# Un_RF_old.net
KiCad netlist of a schematic drawn in EAGLE
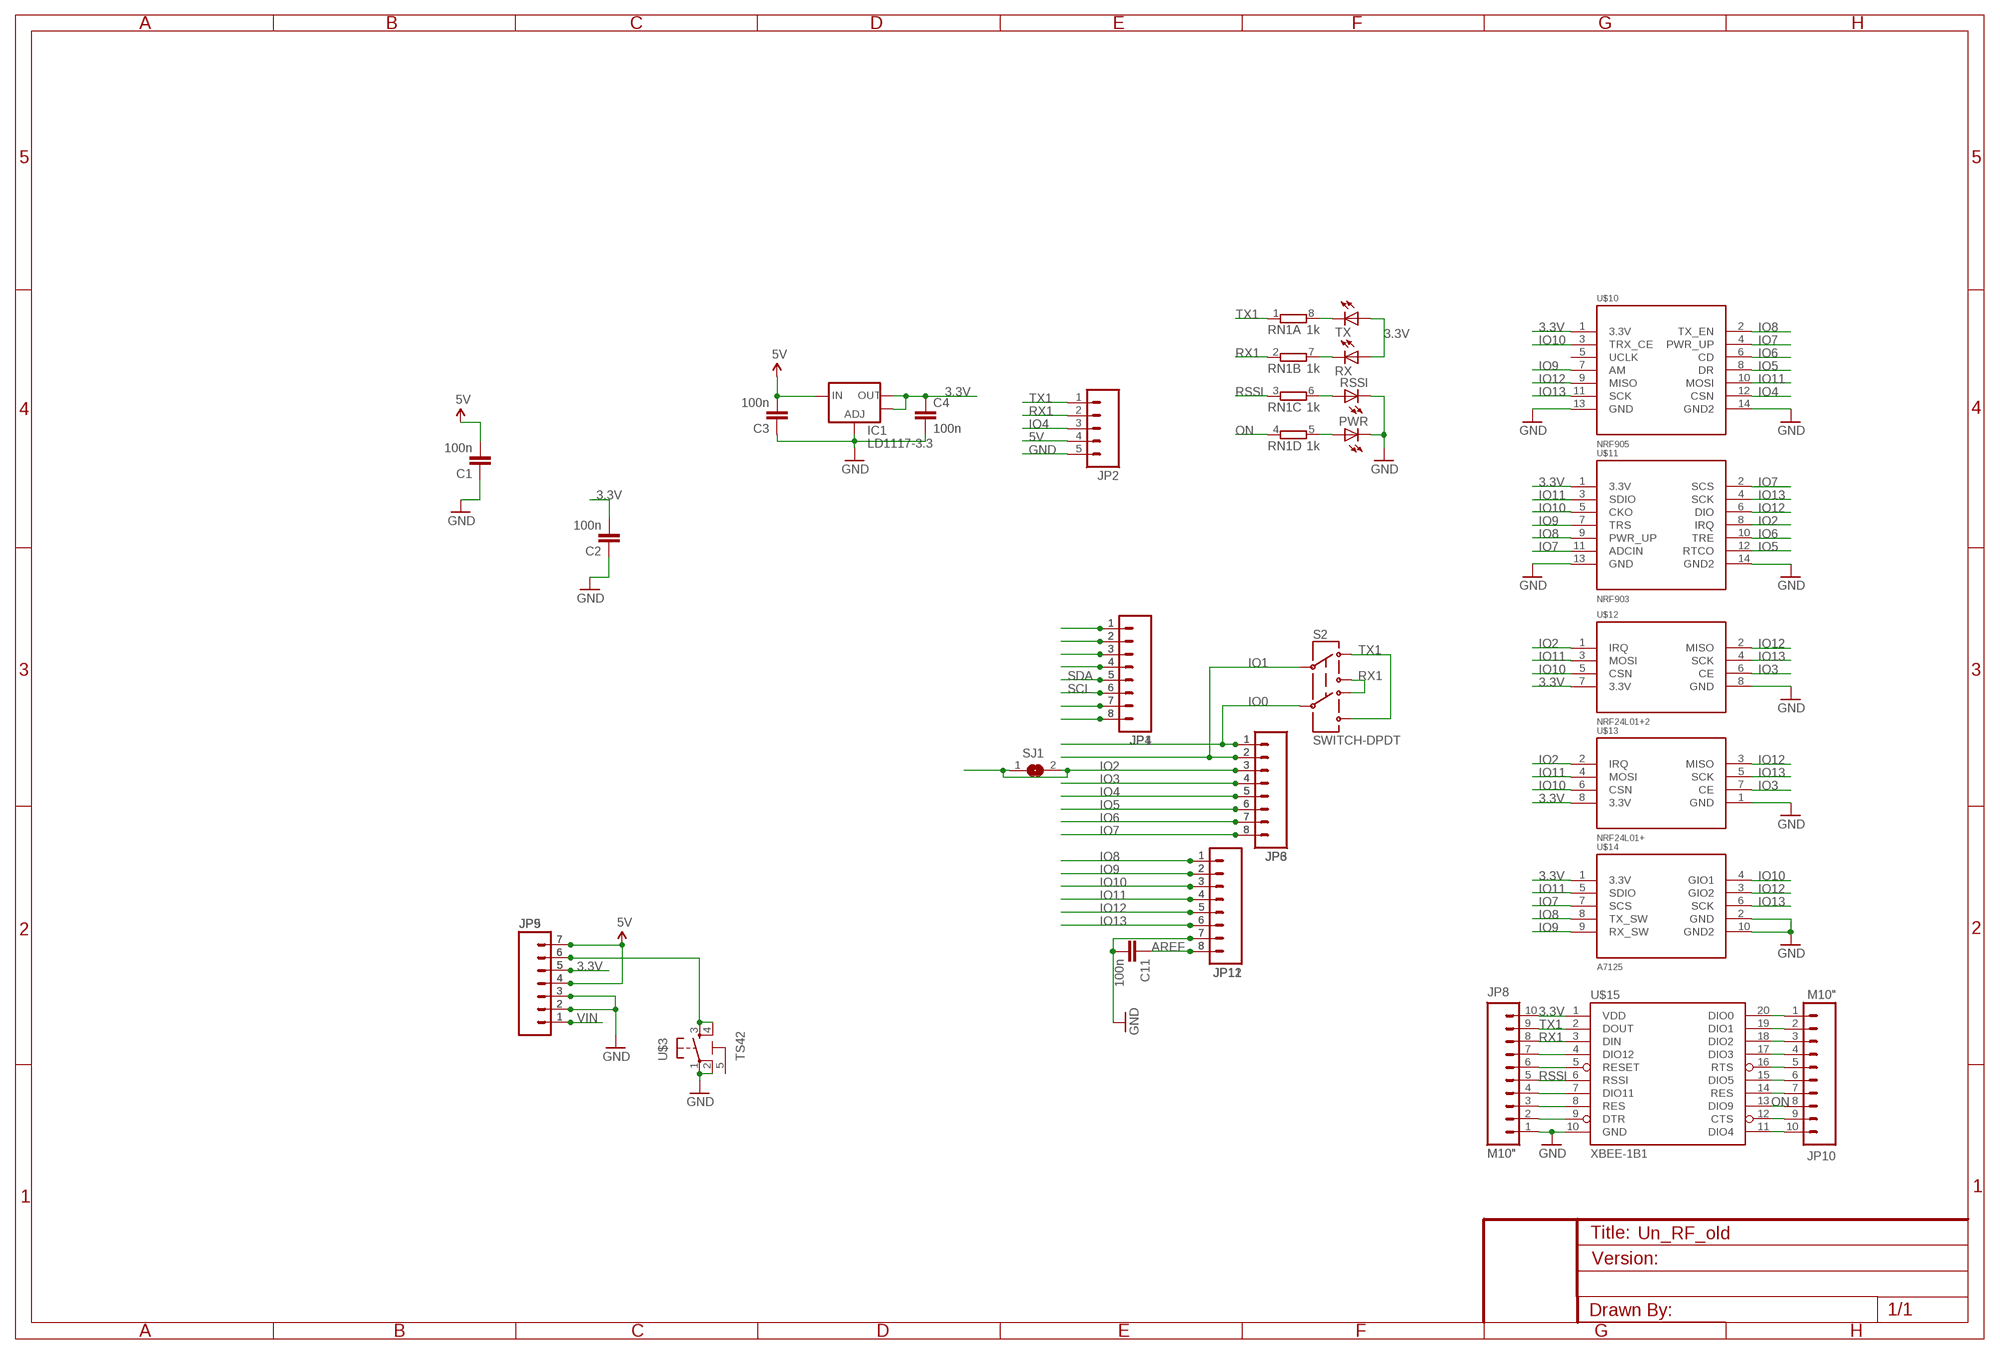
[diagram p0: schematic, sheet 1]

(export (version "E")
  (design (tool "Eeschema 10.0.6"))
  (components
    (comp (ref "C1")
      (value "100n")
      (footprint "eagle-import:0603-CAP")
      (libsource (lib "eagle-import") (part "CAP0603-CAP"))
    )
    (comp (ref "C2")
      (value "100n")
      (footprint "eagle-import:0603-CAP")
      (libsource (lib "eagle-import") (part "CAP0603-CAP"))
    )
    (comp (ref "C3")
      (value "100n")
      (footprint "eagle-import:0603-CAP")
      (libsource (lib "eagle-import") (part "CAP0603-CAP"))
    )
    (comp (ref "C4")
      (value "100n")
      (footprint "eagle-import:0603-CAP")
      (libsource (lib "eagle-import") (part "CAP0603-CAP"))
    )
    (comp (ref "C11")
      (value "100n")
      (footprint "eagle-import:0603-CAP")
      (libsource (lib "eagle-import") (part "CAP0603-CAP"))
    )
    (comp (ref "IC1")
      (value "LD1117-3.3")
      (footprint "eagle-import:SOT223")
      (libsource (lib "eagle-import") (part "V_REG_LM1117SOT223"))
    )
    (comp (ref "JP1")
      (value "M081X08")
      (footprint "eagle-import:1X08")
      (libsource (lib "eagle-import") (part "M081X08"))
    )
    (comp (ref "JP2")
      (value "M05PTH")
      (footprint "eagle-import:1X05")
      (libsource (lib "eagle-import") (part "M05PTH"))
    )
    (comp (ref "JP3")
      (value "M08")
      (footprint "eagle-import:1X08")
      (libsource (lib "eagle-import") (part "M08"))
    )
    (comp (ref "JP4")
      (value "M081X08")
      (footprint "eagle-import:1X08")
      (libsource (lib "eagle-import") (part "M081X08"))
    )
    (comp (ref "JP5")
      (value "M07")
      (footprint "eagle-import:1X07")
      (libsource (lib "eagle-import") (part "M07"))
    )
    (comp (ref "JP6")
      (value "M08")
      (footprint "eagle-import:1X08")
      (libsource (lib "eagle-import") (part "M08"))
    )
    (comp (ref "JP8")
      (value "M10\"")
      (footprint "eagle-import:1X10")
      (libsource (lib "eagle-import") (part "M10{dblquote}"))
    )
    (comp (ref "JP9")
      (value "M07")
      (footprint "eagle-import:1X07")
      (libsource (lib "eagle-import") (part "M07"))
    )
    (comp (ref "JP10")
      (value "M10\"")
      (footprint "eagle-import:1X10")
      (libsource (lib "eagle-import") (part "M10{dblquote}"))
    )
    (comp (ref "JP11")
      (value "M081X08")
      (footprint "eagle-import:1X08")
      (libsource (lib "eagle-import") (part "M081X08"))
    )
    (comp (ref "JP12")
      (value "M081X08")
      (footprint "eagle-import:1X08")
      (libsource (lib "eagle-import") (part "M081X08"))
    )
    (comp (ref "PWR")
      (value "LED0805")
      (footprint "eagle-import:LED-0805")
      (libsource (lib "eagle-import") (part "LED0805"))
    )
    (comp (ref "RN1")
      (value "1k")
      (footprint "eagle-import:CAY16")
      (libsource (lib "eagle-import") (part "4R-NCAY16"))
    )
    (comp (ref "RSSI")
      (value "LED0805")
      (footprint "eagle-import:LED-0805")
      (libsource (lib "eagle-import") (part "LED0805"))
    )
    (comp (ref "RX")
      (value "LED0805")
      (footprint "eagle-import:LED-0805")
      (libsource (lib "eagle-import") (part "LED0805"))
    )
    (comp (ref "S2")
      (value "SWITCH-DPDT")
      (footprint "eagle-import:SWITCH-P2")
      (libsource (lib "eagle-import") (part "SWITCH-DPDT"))
    )
    (comp (ref "SJ1") (value "SJ") (footprint "eagle-import:SJ") (libsource (lib "eagle-import") (part "SJ")))
    (comp (ref "TX")
      (value "LED0805")
      (footprint "eagle-import:LED-0805")
      (libsource (lib "eagle-import") (part "LED0805"))
    )
    (comp (ref "U$3")
      (value "TS42")
      (footprint "eagle-import:TS42")
      (libsource (lib "eagle-import") (part "TS42"))
    )
    (comp (ref "U$10")
      (value "NRF905")
      (footprint "eagle-import:2X7")
      (libsource (lib "eagle-import") (part "NRF905"))
    )
    (comp (ref "U$11")
      (value "NRF903")
      (footprint "eagle-import:2X7")
      (libsource (lib "eagle-import") (part "NRF903"))
    )
    (comp (ref "U$12")
      (value "NRF24L01+2")
      (footprint "eagle-import:2X4")
      (libsource (lib "eagle-import") (part "NRF24L01+2"))
    )
    (comp (ref "U$13")
      (value "NRF24L01+")
      (footprint "eagle-import:1X08")
      (libsource (lib "eagle-import") (part "NRF24L01+"))
    )
    (comp (ref "U$14")
      (value "A7125")
      (footprint "eagle-import:1X10-2MM")
      (libsource (lib "eagle-import") (part "A7125"))
    )
    (comp (ref "U$15")
      (value "XBEE-1B1")
      (footprint "eagle-import:XBEE-1")
      (libsource (lib "eagle-import") (part "XBEE-1B1"))
    )
  )
  (nets
    (net (code "1") (name "/3.3V") (class "Default")
      (node (ref "C2") (pin "2") (pinfunction "2_2") (pintype "passive"))
      (node (ref "C4") (pin "1") (pinfunction "1_1") (pintype "passive"))
      (node (ref "IC1") (pin "2") (pinfunction "OUT_2") (pintype "output"))
      (node (ref "IC1") (pin "4") (pinfunction "OUT_4") (pintype "output"))
      (node (ref "JP5") (pin "5") (pinfunction "5_5") (pintype "passive"))
      (node (ref "JP8") (pin "10") (pinfunction "10_10") (pintype "passive"))
      (node (ref "JP9") (pin "5") (pinfunction "5_5") (pintype "passive"))
      (node (ref "RX") (pin "1") (pinfunction "A_1") (pintype "passive"))
      (node (ref "TX") (pin "1") (pinfunction "A_1") (pintype "passive"))
      (node (ref "U$10") (pin "1") (pinfunction "3.3V_1") (pintype "bidirectional"))
      (node (ref "U$11") (pin "1") (pinfunction "3.3V_1") (pintype "bidirectional"))
      (node (ref "U$12") (pin "7") (pinfunction "3.3V_7") (pintype "bidirectional"))
      (node (ref "U$13") (pin "8") (pinfunction "3.3V_8") (pintype "bidirectional"))
      (node (ref "U$14") (pin "1") (pinfunction "3.3V_1") (pintype "bidirectional"))
      (node (ref "U$15") (pin "1") (pinfunction "VDD_1") (pintype "power_in"))
    )
    (net (code "2") (name "/AREF") (class "Default")
      (node (ref "C11") (pin "1") (pinfunction "1_1") (pintype "passive"))
      (node (ref "JP11") (pin "8") (pinfunction "8_8") (pintype "passive"))
      (node (ref "JP12") (pin "8") (pinfunction "8_8") (pintype "passive"))
    )
    (net (code "3") (name "/IO0") (class "Default")
      (node (ref "JP3") (pin "1") (pinfunction "1_1") (pintype "passive"))
      (node (ref "JP6") (pin "1") (pinfunction "1_1") (pintype "passive"))
      (node (ref "S2") (pin "5") (pinfunction "5_5") (pintype "bidirectional"))
    )
    (net (code "4") (name "/IO1") (class "Default")
      (node (ref "JP3") (pin "2") (pinfunction "2_2") (pintype "passive"))
      (node (ref "JP6") (pin "2") (pinfunction "2_2") (pintype "passive"))
      (node (ref "S2") (pin "2") (pinfunction "2_2") (pintype "bidirectional"))
    )
    (net (code "5") (name "/IO2") (class "Default")
      (node (ref "JP3") (pin "3") (pinfunction "3_3") (pintype "passive"))
      (node (ref "JP6") (pin "3") (pinfunction "3_3") (pintype "passive"))
      (node (ref "SJ1") (pin "1") (pinfunction "1_1") (pintype "passive"))
      (node (ref "SJ1") (pin "2") (pinfunction "2_2") (pintype "passive"))
      (node (ref "U$11") (pin "8") (pinfunction "IRQ_8") (pintype "bidirectional"))
      (node (ref "U$12") (pin "1") (pinfunction "IRQ_1") (pintype "bidirectional"))
      (node (ref "U$13") (pin "2") (pinfunction "IRQ_2") (pintype "bidirectional"))
    )
    (net (code "6") (name "/IO3") (class "Default")
      (node (ref "JP3") (pin "4") (pinfunction "4_4") (pintype "passive"))
      (node (ref "JP6") (pin "4") (pinfunction "4_4") (pintype "passive"))
      (node (ref "U$12") (pin "6") (pinfunction "CE_6") (pintype "bidirectional"))
      (node (ref "U$13") (pin "7") (pinfunction "CE_7") (pintype "bidirectional"))
    )
    (net (code "7") (name "/IO4") (class "Default")
      (node (ref "JP2") (pin "3") (pinfunction "3_3") (pintype "passive"))
      (node (ref "JP3") (pin "5") (pinfunction "5_5") (pintype "passive"))
      (node (ref "JP6") (pin "5") (pinfunction "5_5") (pintype "passive"))
      (node (ref "U$10") (pin "12") (pinfunction "CSN_12") (pintype "bidirectional"))
    )
    (net (code "8") (name "/IO5") (class "Default")
      (node (ref "JP3") (pin "6") (pinfunction "6_6") (pintype "passive"))
      (node (ref "JP6") (pin "6") (pinfunction "6_6") (pintype "passive"))
      (node (ref "U$10") (pin "8") (pinfunction "DR_8") (pintype "bidirectional"))
      (node (ref "U$11") (pin "12") (pinfunction "RTCO_12") (pintype "bidirectional"))
    )
    (net (code "9") (name "/IO6") (class "Default")
      (node (ref "JP3") (pin "7") (pinfunction "7_7") (pintype "passive"))
      (node (ref "JP6") (pin "7") (pinfunction "7_7") (pintype "passive"))
      (node (ref "U$10") (pin "6") (pinfunction "CD_6") (pintype "bidirectional"))
      (node (ref "U$11") (pin "10") (pinfunction "TRE_10") (pintype "bidirectional"))
    )
    (net (code "10") (name "/IO7") (class "Default")
      (node (ref "JP3") (pin "8") (pinfunction "8_8") (pintype "passive"))
      (node (ref "JP6") (pin "8") (pinfunction "8_8") (pintype "passive"))
      (node (ref "U$10") (pin "4") (pinfunction "PWR_UP_4") (pintype "bidirectional"))
      (node (ref "U$11") (pin "11") (pinfunction "ADCIN_11") (pintype "bidirectional"))
      (node (ref "U$11") (pin "2") (pinfunction "SCS_2") (pintype "bidirectional"))
      (node (ref "U$14") (pin "7") (pinfunction "SCS_7") (pintype "bidirectional"))
    )
    (net (code "11") (name "/IO8") (class "Default")
      (node (ref "JP11") (pin "1") (pinfunction "1_1") (pintype "passive"))
      (node (ref "JP12") (pin "1") (pinfunction "1_1") (pintype "passive"))
      (node (ref "U$10") (pin "2") (pinfunction "TX_EN_2") (pintype "bidirectional"))
      (node (ref "U$11") (pin "9") (pinfunction "PWR_UP_9") (pintype "bidirectional"))
      (node (ref "U$14") (pin "8") (pinfunction "TX_SW_8") (pintype "bidirectional"))
    )
    (net (code "12") (name "/IO9") (class "Default")
      (node (ref "JP11") (pin "2") (pinfunction "2_2") (pintype "passive"))
      (node (ref "JP12") (pin "2") (pinfunction "2_2") (pintype "passive"))
      (node (ref "U$10") (pin "7") (pinfunction "AM_7") (pintype "bidirectional"))
      (node (ref "U$11") (pin "7") (pinfunction "TRS_7") (pintype "bidirectional"))
      (node (ref "U$14") (pin "9") (pinfunction "RX_SW_9") (pintype "bidirectional"))
    )
    (net (code "13") (name "/IO10") (class "Default")
      (node (ref "JP11") (pin "3") (pinfunction "3_3") (pintype "passive"))
      (node (ref "JP12") (pin "3") (pinfunction "3_3") (pintype "passive"))
      (node (ref "U$10") (pin "3") (pinfunction "TRX_CE_3") (pintype "bidirectional"))
      (node (ref "U$11") (pin "5") (pinfunction "CKO_5") (pintype "bidirectional"))
      (node (ref "U$12") (pin "5") (pinfunction "CSN_5") (pintype "bidirectional"))
      (node (ref "U$13") (pin "6") (pinfunction "CSN_6") (pintype "bidirectional"))
      (node (ref "U$14") (pin "4") (pinfunction "GIO1_4") (pintype "bidirectional"))
    )
    (net (code "14") (name "/IO11") (class "Default")
      (node (ref "JP11") (pin "4") (pinfunction "4_4") (pintype "passive"))
      (node (ref "JP12") (pin "4") (pinfunction "4_4") (pintype "passive"))
      (node (ref "U$10") (pin "10") (pinfunction "MOSI_10") (pintype "bidirectional"))
      (node (ref "U$11") (pin "3") (pinfunction "SDIO_3") (pintype "bidirectional"))
      (node (ref "U$12") (pin "3") (pinfunction "MOSI_3") (pintype "bidirectional"))
      (node (ref "U$13") (pin "4") (pinfunction "MOSI_4") (pintype "bidirectional"))
      (node (ref "U$14") (pin "5") (pinfunction "SDIO_5") (pintype "bidirectional"))
    )
    (net (code "15") (name "/IO12") (class "Default")
      (node (ref "JP11") (pin "5") (pinfunction "5_5") (pintype "passive"))
      (node (ref "JP12") (pin "5") (pinfunction "5_5") (pintype "passive"))
      (node (ref "U$10") (pin "9") (pinfunction "MISO_9") (pintype "bidirectional"))
      (node (ref "U$11") (pin "6") (pinfunction "DIO_6") (pintype "bidirectional"))
      (node (ref "U$12") (pin "2") (pinfunction "MISO_2") (pintype "bidirectional"))
      (node (ref "U$13") (pin "3") (pinfunction "MISO_3") (pintype "bidirectional"))
      (node (ref "U$14") (pin "3") (pinfunction "GIO2_3") (pintype "bidirectional"))
    )
    (net (code "16") (name "/IO13") (class "Default")
      (node (ref "JP11") (pin "6") (pinfunction "6_6") (pintype "passive"))
      (node (ref "JP12") (pin "6") (pinfunction "6_6") (pintype "passive"))
      (node (ref "U$10") (pin "11") (pinfunction "SCK_11") (pintype "bidirectional"))
      (node (ref "U$11") (pin "4") (pinfunction "SCK_4") (pintype "bidirectional"))
      (node (ref "U$12") (pin "4") (pinfunction "SCK_4") (pintype "bidirectional"))
      (node (ref "U$13") (pin "5") (pinfunction "SCK_5") (pintype "bidirectional"))
      (node (ref "U$14") (pin "6") (pinfunction "SCK_6") (pintype "bidirectional"))
    )
    (net (code "17") (name "/ON") (class "Default")
      (node (ref "JP10") (pin "8") (pinfunction "8_8") (pintype "passive"))
      (node (ref "RN1") (pin "4") (pinfunction "1_4") (pintype "passive"))
      (node (ref "U$15") (pin "13") (pinfunction "DIO9_13") (pintype "bidirectional"))
    )
    (net (code "18") (name "/RSSI") (class "Default")
      (node (ref "JP8") (pin "5") (pinfunction "5_5") (pintype "passive"))
      (node (ref "RN1") (pin "3") (pinfunction "1_3") (pintype "passive"))
      (node (ref "U$15") (pin "6") (pinfunction "RSSI_6") (pintype "bidirectional"))
    )
    (net (code "19") (name "/RX1") (class "Default")
      (node (ref "JP2") (pin "2") (pinfunction "2_2") (pintype "passive"))
      (node (ref "JP8") (pin "8") (pinfunction "8_8") (pintype "passive"))
      (node (ref "RN1") (pin "2") (pinfunction "1_2") (pintype "passive"))
      (node (ref "S2") (pin "3") (pinfunction "3_3") (pintype "bidirectional"))
      (node (ref "S2") (pin "4") (pinfunction "4_4") (pintype "bidirectional"))
      (node (ref "U$15") (pin "3") (pinfunction "DIN_3") (pintype "input"))
    )
    (net (code "20") (name "/SCL") (class "Default")
      (node (ref "JP1") (pin "6") (pinfunction "6_6") (pintype "passive"))
      (node (ref "JP4") (pin "6") (pinfunction "6_6") (pintype "passive"))
    )
    (net (code "21") (name "/SDA") (class "Default")
      (node (ref "JP1") (pin "5") (pinfunction "5_5") (pintype "passive"))
      (node (ref "JP4") (pin "5") (pinfunction "5_5") (pintype "passive"))
    )
    (net (code "22") (name "/TX1") (class "Default")
      (node (ref "JP2") (pin "1") (pinfunction "1_1") (pintype "passive"))
      (node (ref "JP8") (pin "9") (pinfunction "9_9") (pintype "passive"))
      (node (ref "RN1") (pin "1") (pinfunction "1_1") (pintype "passive"))
      (node (ref "S2") (pin "1") (pinfunction "1_1") (pintype "bidirectional"))
      (node (ref "S2") (pin "6") (pinfunction "6_6") (pintype "bidirectional"))
      (node (ref "U$15") (pin "2") (pinfunction "DOUT_2") (pintype "output"))
    )
    (net (code "23") (name "/VIN") (class "Default")
      (node (ref "JP5") (pin "1") (pinfunction "1_1") (pintype "passive"))
      (node (ref "JP9") (pin "1") (pinfunction "1_1") (pintype "passive"))
    )
    (net (code "24") (name "5V") (class "Default")
      (node (ref "C1") (pin "2") (pinfunction "2_2") (pintype "passive"))
      (node (ref "C3") (pin "2") (pinfunction "2_2") (pintype "passive"))
      (node (ref "IC1") (pin "3") (pinfunction "IN_3") (pintype "input"))
      (node (ref "JP2") (pin "4") (pinfunction "4_4") (pintype "passive"))
      (node (ref "JP5") (pin "4") (pinfunction "4_4") (pintype "passive"))
      (node (ref "JP5") (pin "7") (pinfunction "7_7") (pintype "passive"))
      (node (ref "JP9") (pin "4") (pinfunction "4_4") (pintype "passive"))
      (node (ref "JP9") (pin "7") (pinfunction "7_7") (pintype "passive"))
    )
    (net (code "25") (name "GND") (class "Default")
      (node (ref "C1") (pin "1") (pinfunction "1_1") (pintype "passive"))
      (node (ref "C11") (pin "2") (pinfunction "2_2") (pintype "passive"))
      (node (ref "C2") (pin "1") (pinfunction "1_1") (pintype "passive"))
      (node (ref "C3") (pin "1") (pinfunction "1_1") (pintype "passive"))
      (node (ref "C4") (pin "2") (pinfunction "2_2") (pintype "passive"))
      (node (ref "IC1") (pin "1") (pinfunction "ADJ_1") (pintype "input"))
      (node (ref "JP11") (pin "7") (pinfunction "7_7") (pintype "passive"))
      (node (ref "JP12") (pin "7") (pinfunction "7_7") (pintype "passive"))
      (node (ref "JP2") (pin "5") (pinfunction "5_5") (pintype "passive"))
      (node (ref "JP5") (pin "2") (pinfunction "2_2") (pintype "passive"))
      (node (ref "JP5") (pin "3") (pinfunction "3_3") (pintype "passive"))
      (node (ref "JP8") (pin "1") (pinfunction "1_1") (pintype "passive"))
      (node (ref "JP9") (pin "2") (pinfunction "2_2") (pintype "passive"))
      (node (ref "JP9") (pin "3") (pinfunction "3_3") (pintype "passive"))
      (node (ref "PWR") (pin "2") (pinfunction "C_2") (pintype "passive"))
      (node (ref "RSSI") (pin "2") (pinfunction "C_2") (pintype "passive"))
      (node (ref "U$10") (pin "13") (pinfunction "GND_13") (pintype "bidirectional"))
      (node (ref "U$10") (pin "14") (pinfunction "GND2_14") (pintype "bidirectional"))
      (node (ref "U$11") (pin "13") (pinfunction "GND_13") (pintype "bidirectional"))
      (node (ref "U$11") (pin "14") (pinfunction "GND2_14") (pintype "bidirectional"))
      (node (ref "U$12") (pin "8") (pinfunction "GND_8") (pintype "bidirectional"))
      (node (ref "U$13") (pin "1") (pinfunction "GND_1") (pintype "bidirectional"))
      (node (ref "U$14") (pin "10") (pinfunction "GND2_10") (pintype "bidirectional"))
      (node (ref "U$14") (pin "2") (pinfunction "GND_2") (pintype "bidirectional"))
      (node (ref "U$15") (pin "10") (pinfunction "GND_10") (pintype "power_in"))
      (node (ref "U$3") (pin "1") (pinfunction "1_1") (pintype "passive"))
      (node (ref "U$3") (pin "2") (pinfunction "2_2") (pintype "passive"))
    )
    (net (code "26") (name "Net-(JP1-Pad1)") (class "Default")
      (node (ref "JP1") (pin "1") (pinfunction "1_1") (pintype "passive"))
      (node (ref "JP4") (pin "1") (pinfunction "1_1") (pintype "passive"))
    )
    (net (code "27") (name "Net-(JP1-Pad2)") (class "Default")
      (node (ref "JP1") (pin "2") (pinfunction "2_2") (pintype "passive"))
      (node (ref "JP4") (pin "2") (pinfunction "2_2") (pintype "passive"))
    )
    (net (code "28") (name "Net-(JP1-Pad3)") (class "Default")
      (node (ref "JP1") (pin "3") (pinfunction "3_3") (pintype "passive"))
      (node (ref "JP4") (pin "3") (pinfunction "3_3") (pintype "passive"))
    )
    (net (code "29") (name "Net-(JP1-Pad4)") (class "Default")
      (node (ref "JP1") (pin "4") (pinfunction "4_4") (pintype "passive"))
      (node (ref "JP4") (pin "4") (pinfunction "4_4") (pintype "passive"))
    )
    (net (code "30") (name "Net-(JP1-Pad7)") (class "Default")
      (node (ref "JP1") (pin "7") (pinfunction "7_7") (pintype "passive"))
      (node (ref "JP4") (pin "7") (pinfunction "7_7") (pintype "passive"))
    )
    (net (code "31") (name "Net-(JP1-Pad8)") (class "Default")
      (node (ref "JP1") (pin "8") (pinfunction "8_8") (pintype "passive"))
      (node (ref "JP4") (pin "8") (pinfunction "8_8") (pintype "passive"))
    )
    (net (code "32") (name "Net-(JP5-Pad6)") (class "Default")
      (node (ref "JP5") (pin "6") (pinfunction "6_6") (pintype "passive"))
      (node (ref "JP9") (pin "6") (pinfunction "6_6") (pintype "passive"))
      (node (ref "U$3") (pin "3") (pinfunction "3_3") (pintype "passive"))
      (node (ref "U$3") (pin "4") (pinfunction "4_4") (pintype "passive"))
    )
    (net (code "33") (name "Net-(JP8-Pad3)") (class "Default")
      (node (ref "JP8") (pin "3") (pinfunction "3_3") (pintype "passive"))
      (node (ref "U$15") (pin "8") (pinfunction "RES_8") (pintype "bidirectional"))
    )
    (net (code "34") (name "Net-(JP10-Pad7)") (class "Default")
      (node (ref "JP10") (pin "7") (pinfunction "7_7") (pintype "passive"))
      (node (ref "U$15") (pin "14") (pinfunction "RES_14") (pintype "bidirectional"))
    )
    (net (code "35") (name "Net-(PWR-A)") (class "Default")
      (node (ref "PWR") (pin "1") (pinfunction "A_1") (pintype "passive"))
      (node (ref "RN1") (pin "5") (pinfunction "2_5") (pintype "passive"))
    )
    (net (code "36") (name "Net-(RN1A-2)") (class "Default")
      (node (ref "RN1") (pin "8") (pinfunction "2_8") (pintype "passive"))
      (node (ref "TX") (pin "2") (pinfunction "C_2") (pintype "passive"))
    )
    (net (code "37") (name "Net-(RN1B-2)") (class "Default")
      (node (ref "RN1") (pin "7") (pinfunction "2_7") (pintype "passive"))
      (node (ref "RX") (pin "2") (pinfunction "C_2") (pintype "passive"))
    )
    (net (code "38") (name "Net-(RN1C-2)") (class "Default")
      (node (ref "RN1") (pin "6") (pinfunction "2_6") (pintype "passive"))
      (node (ref "RSSI") (pin "1") (pinfunction "A_1") (pintype "passive"))
    )
    (net (code "39") (name "Net-(U$15-CTS)") (class "Default")
      (node (ref "JP10") (pin "9") (pinfunction "9_9") (pintype "passive"))
      (node (ref "U$15") (pin "12") (pinfunction "CTS_12") (pintype "output"))
    )
    (net (code "40") (name "Net-(U$15-DIO0)") (class "Default")
      (node (ref "JP10") (pin "1") (pinfunction "1_1") (pintype "passive"))
      (node (ref "U$15") (pin "20") (pinfunction "DIO0_20") (pintype "bidirectional"))
    )
    (net (code "41") (name "Net-(U$15-DIO1)") (class "Default")
      (node (ref "JP10") (pin "2") (pinfunction "2_2") (pintype "passive"))
      (node (ref "U$15") (pin "19") (pinfunction "DIO1_19") (pintype "bidirectional"))
    )
    (net (code "42") (name "Net-(U$15-DIO2)") (class "Default")
      (node (ref "JP10") (pin "3") (pinfunction "3_3") (pintype "passive"))
      (node (ref "U$15") (pin "18") (pinfunction "DIO2_18") (pintype "bidirectional"))
    )
    (net (code "43") (name "Net-(U$15-DIO3)") (class "Default")
      (node (ref "JP10") (pin "4") (pinfunction "4_4") (pintype "passive"))
      (node (ref "U$15") (pin "17") (pinfunction "DIO3_17") (pintype "bidirectional"))
    )
    (net (code "44") (name "Net-(U$15-DIO4)") (class "Default")
      (node (ref "JP10") (pin "10") (pinfunction "10_10") (pintype "passive"))
      (node (ref "U$15") (pin "11") (pinfunction "DIO4_11") (pintype "bidirectional"))
    )
    (net (code "45") (name "Net-(U$15-DIO5)") (class "Default")
      (node (ref "JP10") (pin "6") (pinfunction "6_6") (pintype "passive"))
      (node (ref "U$15") (pin "15") (pinfunction "DIO5_15") (pintype "bidirectional"))
    )
    (net (code "46") (name "Net-(U$15-DIO11)") (class "Default")
      (node (ref "JP8") (pin "4") (pinfunction "4_4") (pintype "passive"))
      (node (ref "U$15") (pin "7") (pinfunction "DIO11_7") (pintype "bidirectional"))
    )
    (net (code "47") (name "Net-(U$15-DIO12)") (class "Default")
      (node (ref "JP8") (pin "7") (pinfunction "7_7") (pintype "passive"))
      (node (ref "U$15") (pin "4") (pinfunction "DIO12_4") (pintype "bidirectional"))
    )
    (net (code "48") (name "Net-(U$15-DTR)") (class "Default")
      (node (ref "JP8") (pin "2") (pinfunction "2_2") (pintype "passive"))
      (node (ref "U$15") (pin "9") (pinfunction "DTR_9") (pintype "bidirectional"))
    )
    (net (code "49") (name "Net-(U$15-RESET)") (class "Default")
      (node (ref "JP8") (pin "6") (pinfunction "6_6") (pintype "passive"))
      (node (ref "U$15") (pin "5") (pinfunction "RESET_5") (pintype "input"))
    )
    (net (code "50") (name "Net-(U$15-RTS)") (class "Default")
      (node (ref "JP10") (pin "5") (pinfunction "5_5") (pintype "passive"))
      (node (ref "U$15") (pin "16") (pinfunction "RTS_16") (pintype "input"))
    )
    (net (code "51") (name "unconnected-(U$3-Pad5)") (class "Default")
      (node (ref "U$3") (pin "5") (pinfunction "5_5") (pintype "passive"))
    )
    (net (code "52") (name "unconnected-(U$10-UCLK-Pad5)") (class "Default")
      (node (ref "U$10") (pin "5") (pinfunction "UCLK_5") (pintype "bidirectional"))
    )
  )
)
